# SEDRA_HPN.net
KiCad netlist of a schematic drawn in Altium Designer
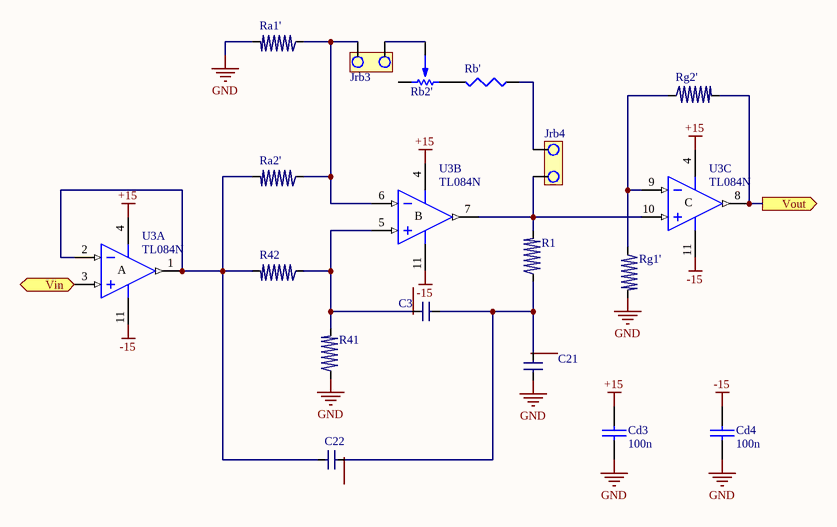
[diagram p0: SEDRA HPN.SchDoc]

(export (version "E")
  (design (tool "Eeschema 10.0.6"))
  (components
    (comp (ref "C3") (value "~") (footprint "SRcap:Model Name") (libsource (lib "") (part "Sheet1_1")))
    (comp (ref "C21") (value "~") (libsource (lib "") (part "Sheet1_1")))
    (comp (ref "C22") (value "~") (footprint "SRcap:Model Name") (libsource (lib "SRcap") (part "Sheet1")))
    (comp (ref "Cd3") (value "100n") (footprint "CAP200") (libsource (lib "LIBEBAL") (part "CAP")))
    (comp (ref "Cd4") (value "100n") (footprint "CAP200") (libsource (lib "LIBEBAL") (part "CAP")))
    (comp (ref "Jrb3") (value "~") (footprint "JUMPER2") (libsource (lib "") (part "JUMPER_1")))
    (comp (ref "Jrb4") (value "~") (footprint "JUMPER2") (libsource (lib "LIBEBAL") (part "JUMPER")))
    (comp (ref "R1") (value "~") (footprint "PCBComponent_1") (libsource (lib "SPres") (part "SPres")))
    (comp (ref "R41") (value "~") (footprint "PCBComponent_1") (libsource (lib "SPres") (part "SPres")))
    (comp (ref "R42") (value "~") (footprint "PCBComponent_1") (libsource (lib "SPres") (part "SPres")))
    (comp (ref "Ra1'") (value "~") (footprint "PCBComponent_1") (libsource (lib "SPres") (part "SPres")))
    (comp (ref "Ra2'") (value "~") (footprint "PCBComponent_1") (libsource (lib "SPres") (part "SPres")))
    (comp (ref "Rb'")
      (value "~")
      (footprint "RES400")
      (description "Resistor")
      (fields (field (name "PUBLISHER") "Altium Limited"))
      (libsource (lib "LIBEBAL") (part "Res3"))
    )
    (comp (ref "Rb2'") (value "~") (footprint "PRESET V") (libsource (lib "LIBEBAL") (part "PRESET")))
    (comp (ref "Rg1'") (value "~") (footprint "PCBComponent_1") (libsource (lib "SPres") (part "SPres")))
    (comp (ref "Rg2'") (value "~") (footprint "PCBComponent_1") (libsource (lib "SPres") (part "SPres")))
    (comp (ref "U3")
      (value "TL084N")
      (footprint "N014")
      (description "JFET-Input Operational Amplifier")
      (fields (field (name "PUBLISHER") "Altium Limited"))
      (libsource (lib "TI Operational Amplifier") (part "TL084N"))
    )
  )
  (nets
    (net (code "1") (name "+15") (class "Default")
      (node (ref "Cd3") (pin "1") (pinfunction "1_1") (pintype "passive"))
      (node (ref "U3") (pin "4") (pinfunction "V+_4") (pintype "power_in"))
    )
    (net (code "2") (name "-15") (class "Default")
      (node (ref "Cd4") (pin "1") (pinfunction "1_1") (pintype "passive"))
      (node (ref "U3") (pin "11") (pinfunction "V-_11") (pintype "power_in"))
    )
    (net (code "3") (name "/Vin") (class "Default")
      (node (ref "U3") (pin "3") (pinfunction "IN+_3") (pintype "input"))
    )
    (net (code "4") (name "/Vout") (class "Default")
      (node (ref "Rg2'") (pin "1") (pinfunction "1_1") (pintype "passive"))
      (node (ref "U3") (pin "8") (pinfunction "OUT_8") (pintype "output"))
    )
    (net (code "5") (name "GND") (class "Default")
      (node (ref "C21") (pin "1") (pinfunction "1_1") (pintype "passive"))
      (node (ref "Cd3") (pin "2") (pinfunction "2_2") (pintype "passive"))
      (node (ref "Cd4") (pin "2") (pinfunction "2_2") (pintype "passive"))
      (node (ref "R41") (pin "2") (pinfunction "2_2") (pintype "passive"))
      (node (ref "Ra1'") (pin "1") (pinfunction "1_1") (pintype "passive"))
      (node (ref "Rg1'") (pin "1") (pinfunction "1_1") (pintype "passive"))
    )
    (net (code "6") (name "Net-(C21-Pad2)") (class "Default")
      (node (ref "C21") (pin "2") (pinfunction "2_2") (pintype "passive"))
      (node (ref "C22") (pin "2") (pinfunction "2_2") (pintype "passive"))
      (node (ref "C3") (pin "1") (pinfunction "1_1") (pintype "passive"))
      (node (ref "R1") (pin "2") (pinfunction "2_2") (pintype "passive"))
    )
    (net (code "7") (name "Net-(Jrb3-Pad2)") (class "Default")
      (node (ref "Jrb3") (pin "2") (pinfunction "2_2") (pintype "passive"))
      (node (ref "Rb2'") (pin "2") (pinfunction "2_2") (pintype "passive"))
    )
    (net (code "8") (name "Net-(Jrb4-Pad2)") (class "Default")
      (node (ref "Jrb4") (pin "2") (pinfunction "2_2") (pintype "passive"))
      (node (ref "Rb'") (pin "1") (pinfunction "1_1") (pintype "passive"))
    )
    (net (code "9") (name "Net-(Rb'-Pad2)") (class "Default")
      (node (ref "Rb'") (pin "2") (pinfunction "2_2") (pintype "passive"))
      (node (ref "Rb2'") (pin "3") (pinfunction "3_3") (pintype "passive"))
    )
    (net (code "10") (name "Net-(U3A-IN-)") (class "Default")
      (node (ref "C22") (pin "1") (pinfunction "1_1") (pintype "passive"))
      (node (ref "R42") (pin "1") (pinfunction "1_1") (pintype "passive"))
      (node (ref "Ra2'") (pin "1") (pinfunction "1_1") (pintype "passive"))
      (node (ref "U3") (pin "1") (pinfunction "OUT_1") (pintype "output"))
      (node (ref "U3") (pin "2") (pinfunction "IN-_2") (pintype "input"))
    )
    (net (code "11") (name "Net-(U3B-IN+)") (class "Default")
      (node (ref "C3") (pin "2") (pinfunction "2_2") (pintype "passive"))
      (node (ref "R41") (pin "1") (pinfunction "1_1") (pintype "passive"))
      (node (ref "R42") (pin "2") (pinfunction "2_2") (pintype "passive"))
      (node (ref "U3") (pin "5") (pinfunction "IN+_5") (pintype "input"))
    )
    (net (code "12") (name "Net-(U3B-IN-)") (class "Default")
      (node (ref "Jrb3") (pin "1") (pinfunction "1_1") (pintype "passive"))
      (node (ref "Ra1'") (pin "2") (pinfunction "2_2") (pintype "passive"))
      (node (ref "Ra2'") (pin "2") (pinfunction "2_2") (pintype "passive"))
      (node (ref "U3") (pin "6") (pinfunction "IN-_6") (pintype "input"))
    )
    (net (code "13") (name "Net-(U3B-OUT)") (class "Default")
      (node (ref "Jrb4") (pin "1") (pinfunction "1_1") (pintype "passive"))
      (node (ref "R1") (pin "1") (pinfunction "1_1") (pintype "passive"))
      (node (ref "U3") (pin "10") (pinfunction "IN+_10") (pintype "input"))
      (node (ref "U3") (pin "7") (pinfunction "OUT_7") (pintype "output"))
    )
    (net (code "14") (name "Net-(U3C-IN-)") (class "Default")
      (node (ref "Rg1'") (pin "2") (pinfunction "2_2") (pintype "passive"))
      (node (ref "Rg2'") (pin "2") (pinfunction "2_2") (pintype "passive"))
      (node (ref "U3") (pin "9") (pinfunction "IN-_9") (pintype "input"))
    )
    (net (code "15") (name "unconnected-(Rb2'-Pad1)") (class "Default")
      (node (ref "Rb2'") (pin "1") (pinfunction "1_1") (pintype "passive"))
    )
  )
)
